# RP.net
KiCad netlist of a schematic drawn in EAGLE
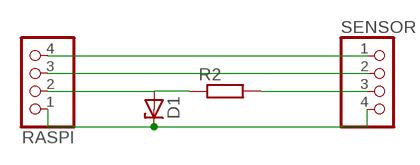
[diagram p0: schematic, sheet 1]

(export (version "E")
  (design (tool "Eeschema 10.0.6"))
  (components
    (comp (ref "D1")
      (value "ZENER-DIODEDO35Z10")
      (footprint "eagle-import:DO35Z10")
      (libsource (lib "eagle-import") (part "ZENER-DIODEDO35Z10"))
    )
    (comp (ref "R2")
      (value "R-EU_0204/7")
      (footprint "eagle-import:0204_7")
      (libsource (lib "eagle-import") (part "R-EU_0204/7"))
    )
    (comp (ref "RASPI")
      (value "PINHD-1X4")
      (footprint "eagle-import:1X04")
      (libsource (lib "eagle-import") (part "PINHD-1X4"))
    )
    (comp (ref "SENSOR")
      (value "PINHD-1X4")
      (footprint "eagle-import:1X04")
      (libsource (lib "eagle-import") (part "PINHD-1X4"))
    )
  )
  (nets
    (net (code "1") (name "Net-(D1-PadA)") (class "Default")
      (node (ref "D1") (pin "A") (pinfunction "A_A") (pintype "passive"))
      (node (ref "R2") (pin "1") (pinfunction "1_1") (pintype "passive"))
      (node (ref "RASPI") (pin "2") (pinfunction "2_2") (pintype "passive"))
    )
    (net (code "2") (name "Net-(D1-PadC)") (class "Default")
      (node (ref "D1") (pin "C") (pinfunction "C_C") (pintype "passive"))
      (node (ref "RASPI") (pin "1") (pinfunction "1_1") (pintype "passive"))
      (node (ref "SENSOR") (pin "4") (pinfunction "4_4") (pintype "passive"))
    )
    (net (code "3") (name "Net-(R2-Pad2)") (class "Default")
      (node (ref "R2") (pin "2") (pinfunction "2_2") (pintype "passive"))
      (node (ref "SENSOR") (pin "3") (pinfunction "3_3") (pintype "passive"))
    )
    (net (code "4") (name "Net-(RASPI-Pad3)") (class "Default")
      (node (ref "RASPI") (pin "3") (pinfunction "3_3") (pintype "passive"))
      (node (ref "SENSOR") (pin "2") (pinfunction "2_2") (pintype "passive"))
    )
    (net (code "5") (name "Net-(RASPI-Pad4)") (class "Default")
      (node (ref "RASPI") (pin "4") (pinfunction "4_4") (pintype "passive"))
      (node (ref "SENSOR") (pin "1") (pinfunction "1_1") (pintype "passive"))
    )
  )
)
